# Schemat.net
KiCad netlist of a schematic drawn in Altium Designer
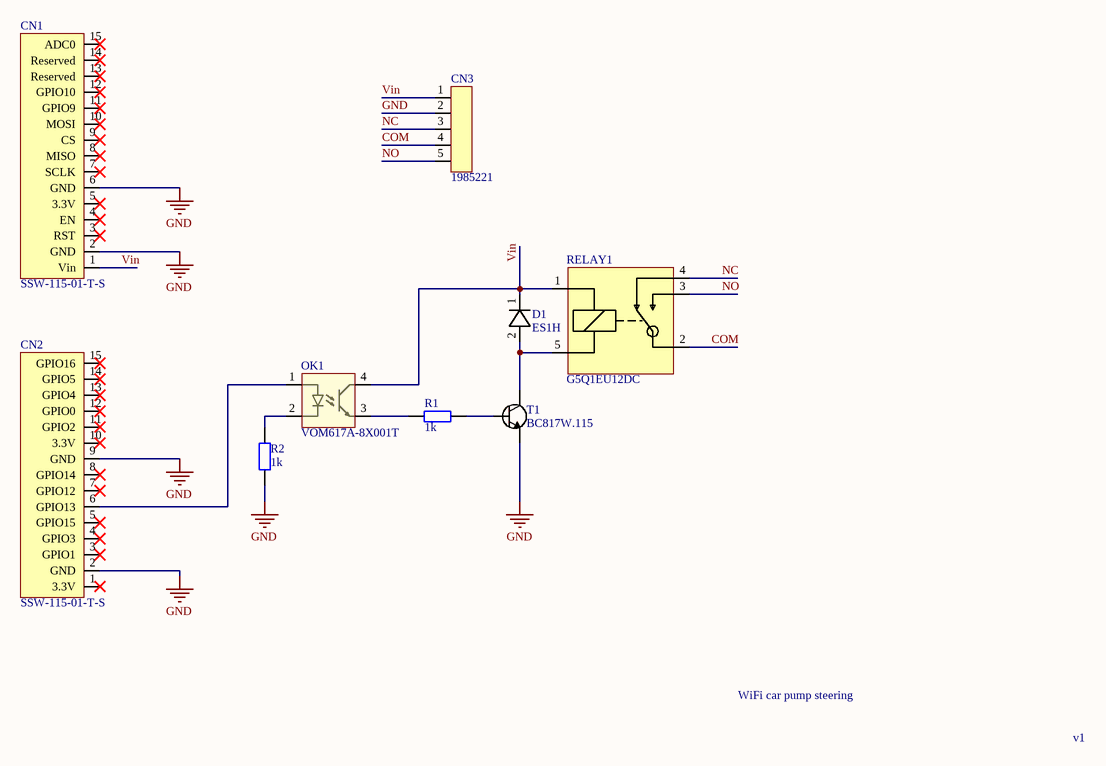
[diagram p0: Schemat.SchDoc]

(export (version "E")
  (design (tool "Eeschema 10.0.6"))
  (components
    (comp (ref "CN1")
      (value "SSW-115-01-T-S")
      (footprint "SSW-115-01-T-S")
      (fields (field (name "MANUFACTURER") "Samtec"))
      (libsource (lib "librariesForWifiPumpSteeringProject") (part "SSW-115-01-T-S"))
    )
    (comp (ref "CN2")
      (value "SSW-115-01-T-S")
      (footprint "SSW-115-01-T-S")
      (fields (field (name "MANUFACTURER") "Samtec"))
      (libsource (lib "librariesForWifiPumpSteeringProject") (part "SSW-115-01-T-S"))
    )
    (comp (ref "CN3")
      (value "1985221")
      (footprint "PTSA 1.5/5-3,5-Z")
      (description "TERM BLOCK 5POS 45DEG 3.5MM PCB")
      (fields (field (name "MANUFACTURER") "Phoenix Contact") (field (name "VOLTAGE") "300V"))
      (libsource (lib "librariesForWifiPumpSteeringProject") (part "1985221"))
    )
    (comp (ref "D1")
      (value "ES1H")
      (footprint "DIOM4326X25N")
      (description "Rectifiers 1A,500V,SUPER FAST Surf Mt Rect")
      (fields (field (name "MANUFACTURER") "Taiwan Semiconductor"))
      (libsource (lib "librariesForWifiPumpSteeringProject") (part "ES1H"))
    )
    (comp (ref "OK1")
      (value "VOM617A-8X001T")
      (footprint "SOP254P700X200-4M")
      (fields (field (name "MANUFACTURER") "Vishay"))
      (libsource (lib "librariesForWifiPumpSteeringProject") (part "VOM617A-8X001T"))
    )
    (comp (ref "R1")
      (value "1206 resistor")
      (footprint "Resistor 1206")
      (description "Resistor: thick film; SMD; 1206; 220O; 0.25W; ±5%; -55÷125°C")
      (fields
        (field (name "MANUFACTURER") "Vishay")
        (field (name "MANUFACTURER PART NUMBER") "CRCW1206220RJNTABC")
        (field (name "RESISTANCE") "1k")
      )
      (libsource (lib "") (part "CRCW1206220RJNTABC_1"))
    )
    (comp (ref "R2")
      (value "1206 resistor")
      (footprint "Resistor 1206")
      (description "Resistor: thick film; SMD; 1206; 220O; 0.25W; ±5%; -55÷125°C")
      (fields
        (field (name "MANUFACTURER") "Vishay")
        (field (name "MANUFACTURER PART NUMBER") "CRCW1206220RJNTABC")
        (field (name "RESISTANCE") "1k")
      )
      (libsource (lib "counter_of_area_parts") (part "CRCW1206220RJNTABC"))
    )
    (comp (ref "RELAY1")
      (value "G5Q1EU12DC")
      (footprint "G5Q-1EU 12DC")
      (description "PCB power relay 12 VDC 400 mW, G5Q1EU12DC, Omron Electronic Components")
      (fields (field (name "MANUFACTURER") "Omron"))
      (libsource (lib "librariesForWifiPumpSteeringProject") (part "G5Q1EU12DC"))
    )
    (comp (ref "T1")
      (value "BC817W.115")
      (footprint "BC817W.115")
      (description "TRANS NPN 45V 0.5A SOT323")
      (fields
        (field (name "MANUFACTURER") "Nexperia USA")
        (field (name "MANUFACTURER PART NUMBER") "BC817W,115")
      )
      (libsource (lib "mosfet_STM32") (part "BC817W,115"))
    )
  )
  (nets
    (net (code "1") (name "/COM") (class "Default")
      (node (ref "CN3") (pin "4") (pinfunction "4_4") (pintype "passive"))
      (node (ref "RELAY1") (pin "2") (pinfunction "COM_2") (pintype "passive"))
    )
    (net (code "2") (name "/NC") (class "Default")
      (node (ref "CN3") (pin "3") (pinfunction "3_3") (pintype "passive"))
      (node (ref "RELAY1") (pin "4") (pinfunction "NC_4") (pintype "passive"))
    )
    (net (code "3") (name "/NO") (class "Default")
      (node (ref "CN3") (pin "5") (pinfunction "5_5") (pintype "passive"))
      (node (ref "RELAY1") (pin "3") (pinfunction "NO_3") (pintype "passive"))
    )
    (net (code "4") (name "/Vin") (class "Default")
      (node (ref "CN1") (pin "1") (pinfunction "3.3V_1") (pintype "passive"))
      (node (ref "CN3") (pin "1") (pinfunction "1_1") (pintype "passive"))
      (node (ref "D1") (pin "1") (pinfunction "C_1") (pintype "passive"))
      (node (ref "OK1") (pin "4") (pinfunction "C_4") (pintype "passive"))
      (node (ref "RELAY1") (pin "1") (pinfunction "A1_1") (pintype "passive"))
    )
    (net (code "5") (name "GND") (class "Default")
      (node (ref "CN1") (pin "2") (pinfunction "GND_2") (pintype "passive"))
      (node (ref "CN1") (pin "6") (pinfunction "GPIO13_6") (pintype "passive"))
      (node (ref "CN2") (pin "2") (pinfunction "GND_2") (pintype "passive"))
      (node (ref "CN2") (pin "9") (pinfunction "GND_9") (pintype "passive"))
      (node (ref "CN3") (pin "2") (pinfunction "2_2") (pintype "passive"))
      (node (ref "R2") (pin "2") (pinfunction "2_2") (pintype "passive"))
      (node (ref "T1") (pin "2") (pinfunction "E_2") (pintype "passive"))
    )
    (net (code "6") (name "Net-(CN2-GPIO13)") (class "Default")
      (node (ref "CN2") (pin "6") (pinfunction "GPIO13_6") (pintype "passive"))
      (node (ref "OK1") (pin "1") (pinfunction "A_1") (pintype "passive"))
    )
    (net (code "7") (name "Net-(D1-A)") (class "Default")
      (node (ref "D1") (pin "2") (pinfunction "A_2") (pintype "passive"))
      (node (ref "RELAY1") (pin "5") (pinfunction "A2_5") (pintype "passive"))
      (node (ref "T1") (pin "3") (pinfunction "C_3") (pintype "passive"))
    )
    (net (code "8") (name "Net-(OK1-C-Pad2)") (class "Default")
      (node (ref "OK1") (pin "2") (pinfunction "C_2") (pintype "passive"))
      (node (ref "R2") (pin "1") (pinfunction "1_1") (pintype "passive"))
    )
    (net (code "9") (name "Net-(OK1-E)") (class "Default")
      (node (ref "OK1") (pin "3") (pinfunction "E_3") (pintype "passive"))
      (node (ref "R1") (pin "1") (pinfunction "1_1") (pintype "passive"))
    )
    (net (code "10") (name "Net-(T1-B)") (class "Default")
      (node (ref "R1") (pin "2") (pinfunction "2_2") (pintype "passive"))
      (node (ref "T1") (pin "1") (pinfunction "B_1") (pintype "passive"))
    )
    (net (code "11") (name "unconnected-(CN1-3.3V-Pad10)") (class "Default")
      (node (ref "CN1") (pin "10") (pinfunction "3.3V_10") (pintype "passive+no_connect"))
    )
    (net (code "12") (name "unconnected-(CN1-GND-Pad9)") (class "Default")
      (node (ref "CN1") (pin "9") (pinfunction "GND_9") (pintype "passive+no_connect"))
    )
    (net (code "13") (name "unconnected-(CN1-GPIO0-Pad12)") (class "Default")
      (node (ref "CN1") (pin "12") (pinfunction "GPIO0_12") (pintype "passive+no_connect"))
    )
    (net (code "14") (name "unconnected-(CN1-GPIO1-Pad3)") (class "Default")
      (node (ref "CN1") (pin "3") (pinfunction "GPIO1_3") (pintype "passive+no_connect"))
    )
    (net (code "15") (name "unconnected-(CN1-GPIO2-Pad11)") (class "Default")
      (node (ref "CN1") (pin "11") (pinfunction "GPIO2_11") (pintype "passive+no_connect"))
    )
    (net (code "16") (name "unconnected-(CN1-GPIO3-Pad4)") (class "Default")
      (node (ref "CN1") (pin "4") (pinfunction "GPIO3_4") (pintype "passive+no_connect"))
    )
    (net (code "17") (name "unconnected-(CN1-GPIO4-Pad13)") (class "Default")
      (node (ref "CN1") (pin "13") (pinfunction "GPIO4_13") (pintype "passive+no_connect"))
    )
    (net (code "18") (name "unconnected-(CN1-GPIO5-Pad14)") (class "Default")
      (node (ref "CN1") (pin "14") (pinfunction "GPIO5_14") (pintype "passive+no_connect"))
    )
    (net (code "19") (name "unconnected-(CN1-GPIO12-Pad7)") (class "Default")
      (node (ref "CN1") (pin "7") (pinfunction "GPIO12_7") (pintype "passive+no_connect"))
    )
    (net (code "20") (name "unconnected-(CN1-GPIO14-Pad8)") (class "Default")
      (node (ref "CN1") (pin "8") (pinfunction "GPIO14_8") (pintype "passive+no_connect"))
    )
    (net (code "21") (name "unconnected-(CN1-GPIO15-Pad5)") (class "Default")
      (node (ref "CN1") (pin "5") (pinfunction "GPIO15_5") (pintype "passive+no_connect"))
    )
    (net (code "22") (name "unconnected-(CN1-GPIO16-Pad15)") (class "Default")
      (node (ref "CN1") (pin "15") (pinfunction "GPIO16_15") (pintype "passive+no_connect"))
    )
    (net (code "23") (name "unconnected-(CN2-3.3V-Pad1)") (class "Default")
      (node (ref "CN2") (pin "1") (pinfunction "3.3V_1") (pintype "passive+no_connect"))
    )
    (net (code "24") (name "unconnected-(CN2-3.3V-Pad10)") (class "Default")
      (node (ref "CN2") (pin "10") (pinfunction "3.3V_10") (pintype "passive+no_connect"))
    )
    (net (code "25") (name "unconnected-(CN2-GPIO0-Pad12)") (class "Default")
      (node (ref "CN2") (pin "12") (pinfunction "GPIO0_12") (pintype "passive+no_connect"))
    )
    (net (code "26") (name "unconnected-(CN2-GPIO1-Pad3)") (class "Default")
      (node (ref "CN2") (pin "3") (pinfunction "GPIO1_3") (pintype "passive+no_connect"))
    )
    (net (code "27") (name "unconnected-(CN2-GPIO2-Pad11)") (class "Default")
      (node (ref "CN2") (pin "11") (pinfunction "GPIO2_11") (pintype "passive+no_connect"))
    )
    (net (code "28") (name "unconnected-(CN2-GPIO3-Pad4)") (class "Default")
      (node (ref "CN2") (pin "4") (pinfunction "GPIO3_4") (pintype "passive+no_connect"))
    )
    (net (code "29") (name "unconnected-(CN2-GPIO4-Pad13)") (class "Default")
      (node (ref "CN2") (pin "13") (pinfunction "GPIO4_13") (pintype "passive+no_connect"))
    )
    (net (code "30") (name "unconnected-(CN2-GPIO5-Pad14)") (class "Default")
      (node (ref "CN2") (pin "14") (pinfunction "GPIO5_14") (pintype "passive+no_connect"))
    )
    (net (code "31") (name "unconnected-(CN2-GPIO12-Pad7)") (class "Default")
      (node (ref "CN2") (pin "7") (pinfunction "GPIO12_7") (pintype "passive+no_connect"))
    )
    (net (code "32") (name "unconnected-(CN2-GPIO14-Pad8)") (class "Default")
      (node (ref "CN2") (pin "8") (pinfunction "GPIO14_8") (pintype "passive+no_connect"))
    )
    (net (code "33") (name "unconnected-(CN2-GPIO15-Pad5)") (class "Default")
      (node (ref "CN2") (pin "5") (pinfunction "GPIO15_5") (pintype "passive+no_connect"))
    )
    (net (code "34") (name "unconnected-(CN2-GPIO16-Pad15)") (class "Default")
      (node (ref "CN2") (pin "15") (pinfunction "GPIO16_15") (pintype "passive+no_connect"))
    )
  )
)
